# HabDroneSCHCO2.net
KiCad netlist of a schematic drawn in EAGLE
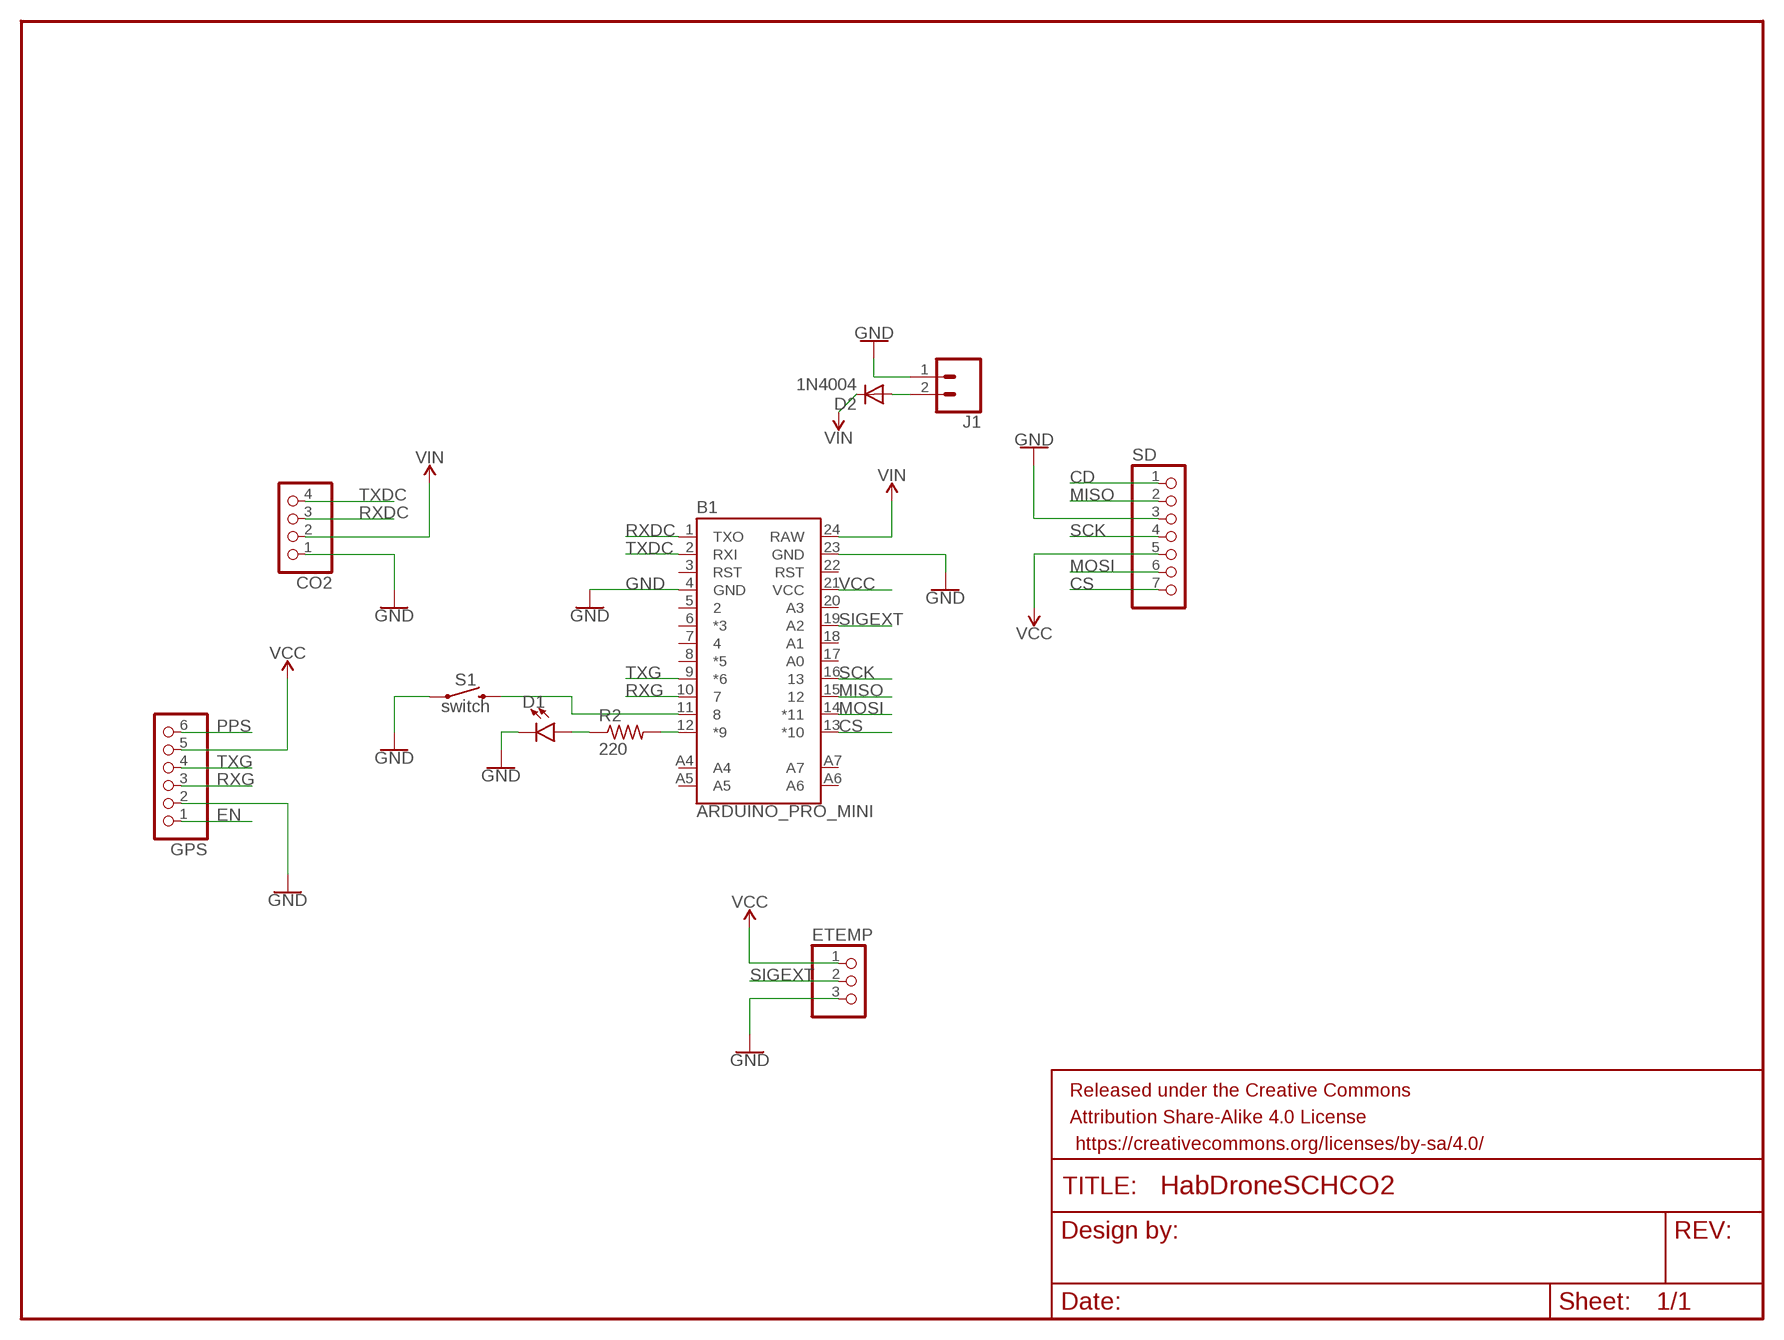
[diagram p0: schematic, sheet 1]

(export (version "E")
  (design (tool "Eeschema 10.0.6"))
  (components
    (comp (ref "B1")
      (value "ARDUINO_PRO_MINI")
      (footprint "eagle-import:ARDUINO_PRO_MINI")
      (libsource (lib "eagle-import") (part "ARDUINO_PRO_MINI"))
    )
    (comp (ref "CO2")
      (value "PINHD-1X4/90")
      (footprint "eagle-import:1X04_90")
      (libsource (lib "eagle-import") (part "PINHD-1X4/90"))
    )
    (comp (ref "D1")
      (value "LED5MM")
      (footprint "eagle-import:LED_5MM")
      (libsource (lib "eagle-import") (part "LED5MM"))
    )
    (comp (ref "D2")
      (value "1N4004")
      (footprint "eagle-import:DO41-10")
      (libsource (lib "eagle-import") (part "1N4004"))
    )
    (comp (ref "ETEMP")
      (value "PINHD-1X3/90")
      (footprint "eagle-import:1X03_90")
      (libsource (lib "eagle-import") (part "PINHD-1X3/90"))
    )
    (comp (ref "FRAME1")
      (value "FRAME-LETTERNO_PACKAGE")
      (footprint "eagle-import:DUMMY")
      (fields (field (name "DESIGNER") "Nobody"))
      (libsource (lib "eagle-import") (part "FRAME-LETTERNO_PACKAGE"))
    )
    (comp (ref "GPS")
      (value "PINHD-1X6/90")
      (footprint "eagle-import:1X06_90")
      (libsource (lib "eagle-import") (part "PINHD-1X6/90"))
    )
    (comp (ref "J1")
      (value "CONN_025MM")
      (footprint "eagle-import:SCREWTERMINAL-5MM-2")
      (libsource (lib "eagle-import") (part "CONN_025MM"))
    )
    (comp (ref "R2")
      (value "220")
      (footprint "eagle-import:VMTA55")
      (libsource (lib "eagle-import") (part "R-US_VMTA55"))
    )
    (comp (ref "S1")
      (value "switch")
      (footprint "eagle-import:TACTILE_SWITCH_PTH_6.0MM")
      (libsource (lib "eagle-import") (part "MOMENTARY-SWITCH-SPST-PTH-6.0MM"))
    )
    (comp (ref "SD")
      (value "PINHD-1X7/90")
      (footprint "eagle-import:1X07_90")
      (libsource (lib "eagle-import") (part "PINHD-1X7/90"))
    )
  )
  (nets
    (net (code "1") (name "/CD") (class "Default")
      (node (ref "SD") (pin "1") (pinfunction "1_1") (pintype "passive"))
    )
    (net (code "2") (name "/CS") (class "Default")
      (node (ref "B1") (pin "13") (pinfunction "*10_13") (pintype "bidirectional"))
      (node (ref "SD") (pin "7") (pinfunction "7_7") (pintype "passive"))
    )
    (net (code "3") (name "/EN") (class "Default")
      (node (ref "GPS") (pin "1") (pinfunction "1_1") (pintype "passive"))
    )
    (net (code "4") (name "/MISO") (class "Default")
      (node (ref "B1") (pin "15") (pinfunction "12_15") (pintype "bidirectional"))
      (node (ref "SD") (pin "2") (pinfunction "2_2") (pintype "passive"))
    )
    (net (code "5") (name "/MOSI") (class "Default")
      (node (ref "B1") (pin "14") (pinfunction "*11_14") (pintype "bidirectional"))
      (node (ref "SD") (pin "6") (pinfunction "6_6") (pintype "passive"))
    )
    (net (code "6") (name "/PPS") (class "Default")
      (node (ref "GPS") (pin "6") (pinfunction "6_6") (pintype "passive"))
    )
    (net (code "7") (name "/RXDC") (class "Default")
      (node (ref "B1") (pin "1") (pinfunction "TXO_1") (pintype "bidirectional"))
      (node (ref "CO2") (pin "3") (pinfunction "3_3") (pintype "passive"))
    )
    (net (code "8") (name "/RXG") (class "Default")
      (node (ref "B1") (pin "10") (pinfunction "7_10") (pintype "bidirectional"))
      (node (ref "GPS") (pin "3") (pinfunction "3_3") (pintype "passive"))
    )
    (net (code "9") (name "/SCK") (class "Default")
      (node (ref "B1") (pin "16") (pinfunction "13_16") (pintype "bidirectional"))
      (node (ref "SD") (pin "4") (pinfunction "4_4") (pintype "passive"))
    )
    (net (code "10") (name "/SIGEXT") (class "Default")
      (node (ref "B1") (pin "19") (pinfunction "A2_19") (pintype "bidirectional"))
      (node (ref "ETEMP") (pin "2") (pinfunction "2_2") (pintype "passive"))
    )
    (net (code "11") (name "/TXDC") (class "Default")
      (node (ref "B1") (pin "2") (pinfunction "RXI_2") (pintype "bidirectional"))
      (node (ref "CO2") (pin "4") (pinfunction "4_4") (pintype "passive"))
    )
    (net (code "12") (name "/TXG") (class "Default")
      (node (ref "B1") (pin "9") (pinfunction "*6_9") (pintype "bidirectional"))
      (node (ref "GPS") (pin "4") (pinfunction "4_4") (pintype "passive"))
    )
    (net (code "13") (name "GND") (class "Default")
      (node (ref "B1") (pin "23") (pinfunction "GND_23") (pintype "power_in"))
      (node (ref "B1") (pin "4") (pinfunction "GND_4") (pintype "power_in"))
      (node (ref "CO2") (pin "1") (pinfunction "1_1") (pintype "passive"))
      (node (ref "D1") (pin "K") (pinfunction "C_K") (pintype "passive"))
      (node (ref "ETEMP") (pin "3") (pinfunction "3_3") (pintype "passive"))
      (node (ref "GPS") (pin "2") (pinfunction "2_2") (pintype "passive"))
      (node (ref "J1") (pin "1") (pinfunction "1_1") (pintype "passive"))
      (node (ref "S1") (pin "1") (pinfunction "1_1") (pintype "passive"))
      (node (ref "SD") (pin "3") (pinfunction "3_3") (pintype "passive"))
    )
    (net (code "14") (name "Net-(B1-*9)") (class "Default")
      (node (ref "B1") (pin "12") (pinfunction "*9_12") (pintype "bidirectional"))
      (node (ref "R2") (pin "2") (pinfunction "2_2") (pintype "passive"))
    )
    (net (code "15") (name "Net-(B1-8)") (class "Default")
      (node (ref "B1") (pin "11") (pinfunction "8_11") (pintype "bidirectional"))
      (node (ref "S1") (pin "3") (pinfunction "2_3") (pintype "passive"))
    )
    (net (code "16") (name "Net-(D1-PadA)") (class "Default")
      (node (ref "D1") (pin "A") (pinfunction "A_A") (pintype "passive"))
      (node (ref "R2") (pin "1") (pinfunction "1_1") (pintype "passive"))
    )
    (net (code "17") (name "Net-(D2-PadA)") (class "Default")
      (node (ref "D2") (pin "A") (pinfunction "A_A") (pintype "passive"))
      (node (ref "J1") (pin "2") (pinfunction "2_2") (pintype "passive"))
    )
    (net (code "18") (name "VCC") (class "Default")
      (node (ref "B1") (pin "21") (pinfunction "VCC_21") (pintype "power_in"))
      (node (ref "ETEMP") (pin "1") (pinfunction "1_1") (pintype "passive"))
      (node (ref "GPS") (pin "5") (pinfunction "5_5") (pintype "passive"))
      (node (ref "SD") (pin "5") (pinfunction "5_5") (pintype "passive"))
    )
    (net (code "19") (name "VIN") (class "Default")
      (node (ref "B1") (pin "24") (pinfunction "RAW_24") (pintype "power_in"))
      (node (ref "CO2") (pin "2") (pinfunction "2_2") (pintype "passive"))
      (node (ref "D2") (pin "C") (pinfunction "C_C") (pintype "passive"))
    )
    (net (code "20") (name "unconnected-(B1-*3-Pad6)") (class "Default")
      (node (ref "B1") (pin "6") (pinfunction "*3_6") (pintype "bidirectional"))
    )
    (net (code "21") (name "unconnected-(B1-*5-Pad8)") (class "Default")
      (node (ref "B1") (pin "8") (pinfunction "*5_8") (pintype "bidirectional"))
    )
    (net (code "22") (name "unconnected-(B1-2-Pad5)") (class "Default")
      (node (ref "B1") (pin "5") (pinfunction "2_5") (pintype "bidirectional"))
    )
    (net (code "23") (name "unconnected-(B1-4-Pad7)") (class "Default")
      (node (ref "B1") (pin "7") (pinfunction "4_7") (pintype "bidirectional"))
    )
    (net (code "24") (name "unconnected-(B1-A0-Pad17)") (class "Default")
      (node (ref "B1") (pin "17") (pinfunction "A0_17") (pintype "bidirectional"))
    )
    (net (code "25") (name "unconnected-(B1-A1-Pad18)") (class "Default")
      (node (ref "B1") (pin "18") (pinfunction "A1_18") (pintype "bidirectional"))
    )
    (net (code "26") (name "unconnected-(B1-A3-Pad20)") (class "Default")
      (node (ref "B1") (pin "20") (pinfunction "A3_20") (pintype "bidirectional"))
    )
    (net (code "27") (name "unconnected-(B1-PadA4)") (class "Default")
      (node (ref "B1") (pin "A4") (pinfunction "A4_A4") (pintype "bidirectional"))
    )
    (net (code "28") (name "unconnected-(B1-PadA5)") (class "Default")
      (node (ref "B1") (pin "A5") (pinfunction "A5_A5") (pintype "bidirectional"))
    )
    (net (code "29") (name "unconnected-(B1-PadA6)") (class "Default")
      (node (ref "B1") (pin "A6") (pinfunction "A6_A6") (pintype "bidirectional"))
    )
    (net (code "30") (name "unconnected-(B1-PadA7)") (class "Default")
      (node (ref "B1") (pin "A7") (pinfunction "A7_A7") (pintype "bidirectional"))
    )
    (net (code "31") (name "unconnected-(B1-RST-Pad3)") (class "Default")
      (node (ref "B1") (pin "3") (pinfunction "RST_3") (pintype "bidirectional"))
    )
    (net (code "32") (name "unconnected-(B1-RST-Pad22)") (class "Default")
      (node (ref "B1") (pin "22") (pinfunction "RST_22") (pintype "bidirectional"))
    )
  )
)
